# 05_ZYNQ_BANK0_1_34_35.net
KiCad netlist of a schematic drawn in Altium Designer
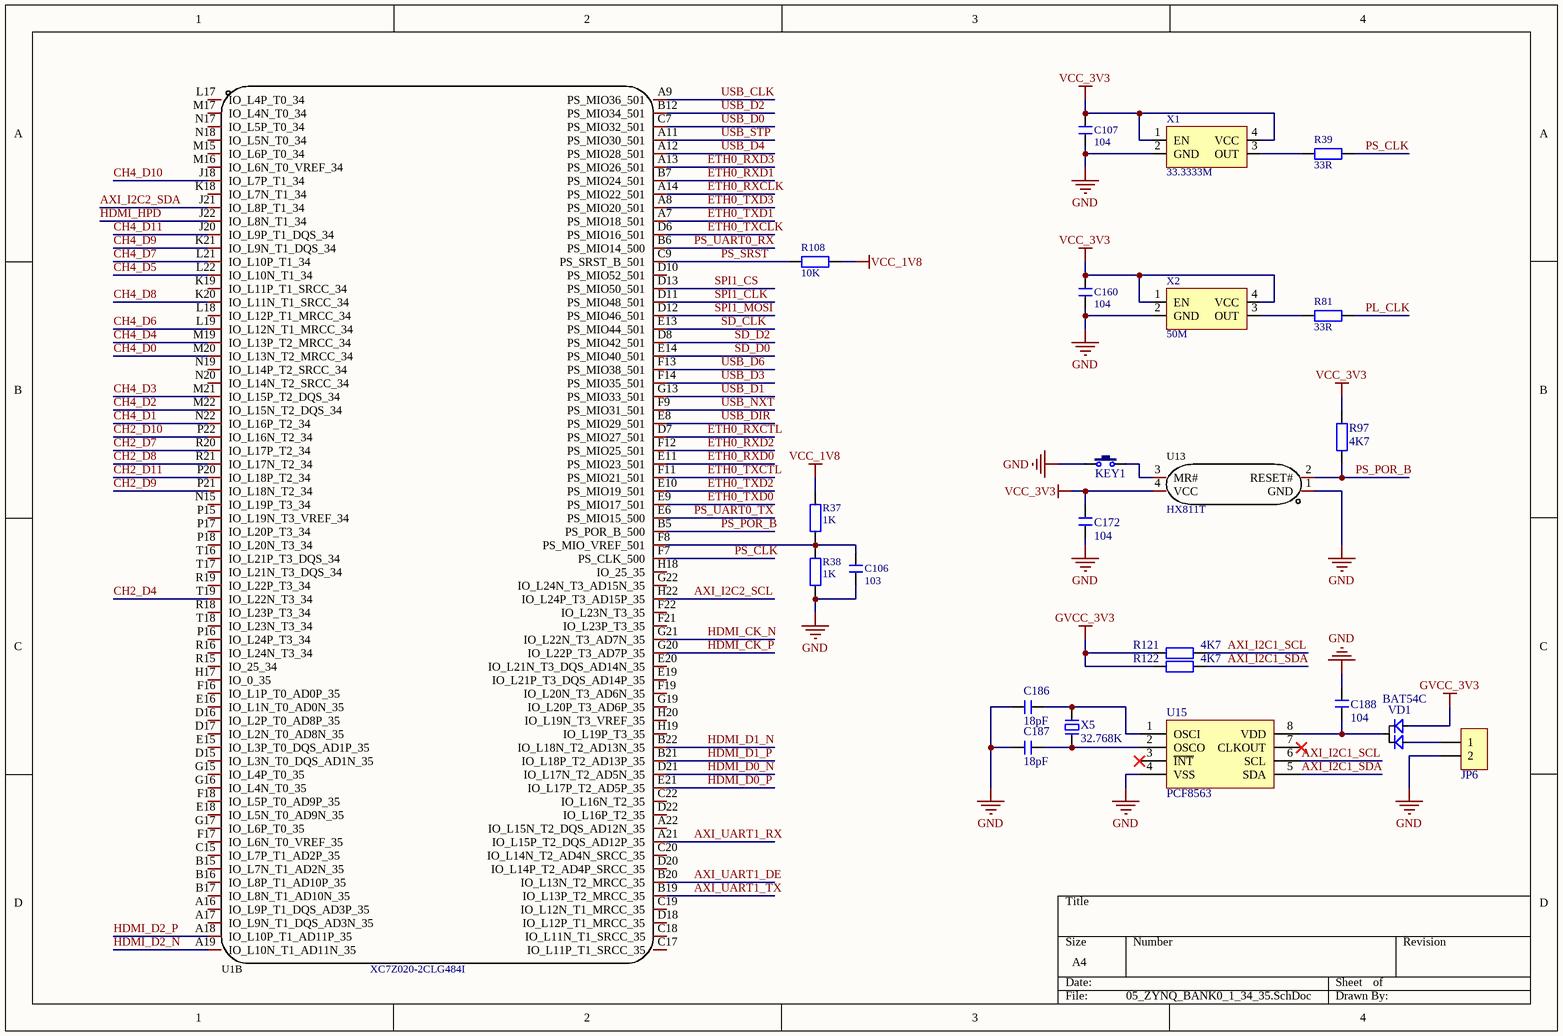
[diagram p0: 05_ZYNQ_BANK0_1_34_35.SchDoc]

(export (version "E")
  (design (tool "Eeschema 10.0.6"))
  (components
    (comp (ref "C106")
      (value "103")
      (footprint "C 0402")
      (description "无极性贴片电容")
      (fields (field (name "版权归属") "源创客"))
      (libsource (lib "STM32MP157核心板封装库V1.2") (part "C"))
    )
    (comp (ref "C107")
      (value "104")
      (footprint "C 0402")
      (description "无极性贴片电容")
      (fields (field (name "版权归属") "源创客"))
      (libsource (lib "STM32MP157核心板封装库V1.2") (part "C"))
    )
    (comp (ref "C160")
      (value "104")
      (footprint "C 0402")
      (description "无极性贴片电容")
      (fields (field (name "版权归属") "源创客"))
      (libsource (lib "STM32MP157核心板封装库V1.2") (part "C"))
    )
    (comp (ref "C172")
      (value "104")
      (footprint "C 0402")
      (description "无极性贴片电容")
      (fields (field (name "版权归属") "源创客"))
      (libsource (lib "STM32MP15x底板封装库V1.4") (part "C"))
    )
    (comp (ref "C186")
      (value "18pF")
      (footprint "C 0603")
      (description "无极性贴片电容")
      (fields (field (name "版权归属") "源创客"))
      (libsource (lib "STM32MP15x底板封装库V1.4") (part "C"))
    )
    (comp (ref "C187")
      (value "18pF")
      (footprint "C 0603")
      (description "无极性贴片电容")
      (fields (field (name "版权归属") "源创客"))
      (libsource (lib "STM32MP15x底板封装库V1.4") (part "C"))
    )
    (comp (ref "C188")
      (value "104")
      (footprint "C 0603")
      (description "无极性贴片电容")
      (fields (field (name "版权归属") "源创客"))
      (libsource (lib "STM32MP15x底板封装库V1.4") (part "C"))
    )
    (comp (ref "JP6")
      (value "HDR-1X2")
      (footprint "SH1.0")
      (description "2P接插件")
      (fields (field (name "版权归属") "源创客"))
      (libsource (lib "4.5   - 接插件-脚距2.54") (part "Header 2"))
    )
    (comp (ref "KEY1")
      (value "KEY")
      (footprint "ButtonTACT_3x4x2_180")
      (description "按键")
      (fields (field (name "版权归属") "源创客"))
      (libsource (lib "STM32MP15x底板封装库V1.4") (part "KEY"))
    )
    (comp (ref "R37")
      (value "1K")
      (footprint "R 0402")
      (description "贴片电阻")
      (fields (field (name "版权归属") "源创客"))
      (libsource (lib "STM32MP157核心板封装库V1.2") (part "R"))
    )
    (comp (ref "R38")
      (value "1K")
      (footprint "R 0402")
      (description "贴片电阻")
      (fields (field (name "版权归属") "源创客"))
      (libsource (lib "STM32MP157核心板封装库V1.2") (part "R"))
    )
    (comp (ref "R39")
      (value "33R")
      (footprint "R 0402")
      (description "贴片电阻")
      (fields (field (name "版权归属") "源创客"))
      (libsource (lib "STM32MP157核心板封装库V1.2") (part "R"))
    )
    (comp (ref "R81")
      (value "33R")
      (footprint "R 0402")
      (description "贴片电阻")
      (fields (field (name "版权归属") "源创客"))
      (libsource (lib "STM32MP157核心板封装库V1.2") (part "R"))
    )
    (comp (ref "R97")
      (value "4K7")
      (footprint "R 0402")
      (description "贴片电阻")
      (fields (field (name "版权归属") "源创客"))
      (libsource (lib "STM32MP15x底板封装库V1.4") (part "R"))
    )
    (comp (ref "R108")
      (value "10K")
      (footprint "R 0402")
      (description "贴片电阻")
      (fields (field (name "版权归属") "源创客"))
      (libsource (lib "STM32MP157核心板封装库V1.2") (part "R"))
    )
    (comp (ref "R121")
      (value "4K7")
      (footprint "R 0603")
      (description "贴片电阻")
      (fields (field (name "版权归属") "源创客"))
      (libsource (lib "STM32MP15x底板封装库V1.4") (part "R"))
    )
    (comp (ref "R122")
      (value "4K7")
      (footprint "R 0603")
      (description "贴片电阻")
      (fields (field (name "版权归属") "源创客"))
      (libsource (lib "STM32MP15x底板封装库V1.4") (part "R"))
    )
    (comp (ref "U1")
      (value "XC7Z020-2CLG484I")
      (footprint "FPBGA-484_L19.0-W19.0-R22-C22-P0.80-BL")
      (fields (field (name "MANUFACTURER") "XILINX(赛灵思)"))
      (libsource (lib "XC7Z020-2CLG484I1") (part "XC7Z020-2CLG484I"))
    )
    (comp (ref "U13")
      (value "HX811T")
      (footprint "SOT143")
      (fields (field (name "MANUFACTURER") "HX(恒佳兴)"))
      (libsource (lib "HX811T") (part "HX811T"))
    )
    (comp (ref "U15")
      (value "PCF8563")
      (footprint "SOP8_N")
      (libsource (lib "STM32MP15x底板封装库V1.4") (part "PCF8563"))
    )
    (comp (ref "VD1")
      (value "BAT54C")
      (footprint "SOT23-3N")
      (description "肖特基二极管（双）")
      (libsource (lib "STM32MP15x底板封装库V1.4") (part "BAT54C"))
    )
    (comp (ref "X1")
      (value "33.3333M")
      (footprint "XTAL-3225 - S")
      (description "4脚有源晶振")
      (fields (field (name "版权归属") "源创客"))
      (libsource (lib "STM32MP157核心板封装库V1.2") (part "XTAL-4P_S"))
    )
    (comp (ref "X2")
      (value "50M")
      (footprint "XTAL-3225 - S")
      (description "4脚有源晶振")
      (fields (field (name "版权归属") "源创客"))
      (libsource (lib "STM32MP157核心板封装库V1.2") (part "XTAL-4P_S"))
    )
    (comp (ref "X5")
      (value "32.768K")
      (footprint "XTAL-3215")
      (description "2脚无源晶振")
      (fields (field (name "版权归属") "源创客"))
      (libsource (lib "STM32MP15x底板封装库V1.4") (part "XTAL-2P"))
    )
  )
  (nets
    (net (code "1") (name "/AXI_I2C1_SCL") (class "Default")
      (node (ref "R121") (pin "2") (pinfunction "2_2") (pintype "passive"))
      (node (ref "U15") (pin "6") (pinfunction "SCL_6") (pintype "passive"))
    )
    (net (code "2") (name "/AXI_I2C1_SDA") (class "Default")
      (node (ref "R122") (pin "2") (pinfunction "2_2") (pintype "passive"))
      (node (ref "U15") (pin "5") (pinfunction "SDA_5") (pintype "passive"))
    )
    (net (code "3") (name "/AXI_I2C2_SCL") (class "Default")
      (node (ref "U1") (pin "H22") (pinfunction "IO_L24P_T3_AD15P_35_H22") (pintype "passive"))
    )
    (net (code "4") (name "/AXI_I2C2_SDA") (class "Default")
      (node (ref "U1") (pin "J21") (pinfunction "IO_L8P_T1_34_J21") (pintype "passive"))
    )
    (net (code "5") (name "/AXI_UART1_DE") (class "Default")
      (node (ref "U1") (pin "B20") (pinfunction "IO_L13N_T2_MRCC_35_B20") (pintype "passive"))
    )
    (net (code "6") (name "/AXI_UART1_RX") (class "Default")
      (node (ref "U1") (pin "A21") (pinfunction "IO_L15P_T2_DQS_AD12P_35_A21") (pintype "passive"))
    )
    (net (code "7") (name "/AXI_UART1_TX") (class "Default")
      (node (ref "U1") (pin "B19") (pinfunction "IO_L13P_T2_MRCC_35_B19") (pintype "passive"))
    )
    (net (code "8") (name "/CH2_D4") (class "Default")
      (node (ref "U1") (pin "T19") (pinfunction "IO_L22N_T3_34_T19") (pintype "passive"))
    )
    (net (code "9") (name "/CH2_D7") (class "Default")
      (node (ref "U1") (pin "R20") (pinfunction "IO_L17P_T2_34_R20") (pintype "passive"))
    )
    (net (code "10") (name "/CH2_D8") (class "Default")
      (node (ref "U1") (pin "R21") (pinfunction "IO_L17N_T2_34_R21") (pintype "passive"))
    )
    (net (code "11") (name "/CH2_D9") (class "Default")
      (node (ref "U1") (pin "P21") (pinfunction "IO_L18N_T2_34_P21") (pintype "passive"))
    )
    (net (code "12") (name "/CH2_D10") (class "Default")
      (node (ref "U1") (pin "P22") (pinfunction "IO_L16N_T2_34_P22") (pintype "passive"))
    )
    (net (code "13") (name "/CH2_D11") (class "Default")
      (node (ref "U1") (pin "P20") (pinfunction "IO_L18P_T2_34_P20") (pintype "passive"))
    )
    (net (code "14") (name "/CH4_D0") (class "Default")
      (node (ref "U1") (pin "M20") (pinfunction "IO_L13N_T2_MRCC_34_M20") (pintype "passive"))
    )
    (net (code "15") (name "/CH4_D1") (class "Default")
      (node (ref "U1") (pin "N22") (pinfunction "IO_L16P_T2_34_N22") (pintype "passive"))
    )
    (net (code "16") (name "/CH4_D2") (class "Default")
      (node (ref "U1") (pin "M22") (pinfunction "IO_L15N_T2_DQS_34_M22") (pintype "passive"))
    )
    (net (code "17") (name "/CH4_D3") (class "Default")
      (node (ref "U1") (pin "M21") (pinfunction "IO_L15P_T2_DQS_34_M21") (pintype "passive"))
    )
    (net (code "18") (name "/CH4_D4") (class "Default")
      (node (ref "U1") (pin "M19") (pinfunction "IO_L13P_T2_MRCC_34_M19") (pintype "passive"))
    )
    (net (code "19") (name "/CH4_D5") (class "Default")
      (node (ref "U1") (pin "L22") (pinfunction "IO_L10N_T1_34_L22") (pintype "passive"))
    )
    (net (code "20") (name "/CH4_D6") (class "Default")
      (node (ref "U1") (pin "L19") (pinfunction "IO_L12N_T1_MRCC_34_L19") (pintype "passive"))
    )
    (net (code "21") (name "/CH4_D7") (class "Default")
      (node (ref "U1") (pin "L21") (pinfunction "IO_L10P_T1_34_L21") (pintype "passive"))
    )
    (net (code "22") (name "/CH4_D8") (class "Default")
      (node (ref "U1") (pin "K20") (pinfunction "IO_L11N_T1_SRCC_34_K20") (pintype "passive"))
    )
    (net (code "23") (name "/CH4_D9") (class "Default")
      (node (ref "U1") (pin "K21") (pinfunction "IO_L9N_T1_DQS_34_K21") (pintype "passive"))
    )
    (net (code "24") (name "/CH4_D10") (class "Default")
      (node (ref "U1") (pin "J18") (pinfunction "IO_L7P_T1_34_J18") (pintype "passive"))
    )
    (net (code "25") (name "/CH4_D11") (class "Default")
      (node (ref "U1") (pin "J20") (pinfunction "IO_L9P_T1_DQS_34_J20") (pintype "passive"))
    )
    (net (code "26") (name "/ETH0_RXCLK") (class "Default")
      (node (ref "U1") (pin "A14") (pinfunction "PS_MIO22_501_A14") (pintype "passive"))
    )
    (net (code "27") (name "/ETH0_RXCTL") (class "Default")
      (node (ref "U1") (pin "D7") (pinfunction "PS_MIO27_501_D7") (pintype "passive"))
    )
    (net (code "28") (name "/ETH0_RXD0") (class "Default")
      (node (ref "U1") (pin "E11") (pinfunction "PS_MIO23_501_E11") (pintype "passive"))
    )
    (net (code "29") (name "/ETH0_RXD1") (class "Default")
      (node (ref "U1") (pin "B7") (pinfunction "PS_MIO24_501_B7") (pintype "passive"))
    )
    (net (code "30") (name "/ETH0_RXD2") (class "Default")
      (node (ref "U1") (pin "F12") (pinfunction "PS_MIO25_501_F12") (pintype "passive"))
    )
    (net (code "31") (name "/ETH0_RXD3") (class "Default")
      (node (ref "U1") (pin "A13") (pinfunction "PS_MIO26_501_A13") (pintype "passive"))
    )
    (net (code "32") (name "/ETH0_TXCLK") (class "Default")
      (node (ref "U1") (pin "D6") (pinfunction "PS_MIO16_501_D6") (pintype "passive"))
    )
    (net (code "33") (name "/ETH0_TXCTL") (class "Default")
      (node (ref "U1") (pin "F11") (pinfunction "PS_MIO21_501_F11") (pintype "passive"))
    )
    (net (code "34") (name "/ETH0_TXD0") (class "Default")
      (node (ref "U1") (pin "E9") (pinfunction "PS_MIO17_501_E9") (pintype "passive"))
    )
    (net (code "35") (name "/ETH0_TXD1") (class "Default")
      (node (ref "U1") (pin "A7") (pinfunction "PS_MIO18_501_A7") (pintype "passive"))
    )
    (net (code "36") (name "/ETH0_TXD2") (class "Default")
      (node (ref "U1") (pin "E10") (pinfunction "PS_MIO19_501_E10") (pintype "passive"))
    )
    (net (code "37") (name "/ETH0_TXD3") (class "Default")
      (node (ref "U1") (pin "A8") (pinfunction "PS_MIO20_501_A8") (pintype "passive"))
    )
    (net (code "38") (name "/HDMI_CK_N") (class "Default")
      (node (ref "U1") (pin "G21") (pinfunction "IO_L22N_T3_AD7N_35_G21") (pintype "passive"))
    )
    (net (code "39") (name "/HDMI_CK_P") (class "Default")
      (node (ref "U1") (pin "G20") (pinfunction "IO_L22P_T3_AD7P_35_G20") (pintype "passive"))
    )
    (net (code "40") (name "/HDMI_D0_N") (class "Default")
      (node (ref "U1") (pin "D21") (pinfunction "IO_L17N_T2_AD5N_35_D21") (pintype "passive"))
    )
    (net (code "41") (name "/HDMI_D0_P") (class "Default")
      (node (ref "U1") (pin "E21") (pinfunction "IO_L17P_T2_AD5P_35_E21") (pintype "passive"))
    )
    (net (code "42") (name "/HDMI_D1_N") (class "Default")
      (node (ref "U1") (pin "B22") (pinfunction "IO_L18N_T2_AD13N_35_B22") (pintype "passive"))
    )
    (net (code "43") (name "/HDMI_D1_P") (class "Default")
      (node (ref "U1") (pin "B21") (pinfunction "IO_L18P_T2_AD13P_35_B21") (pintype "passive"))
    )
    (net (code "44") (name "/HDMI_D2_N") (class "Default")
      (node (ref "U1") (pin "A19") (pinfunction "IO_L10N_T1_AD11N_35_A19") (pintype "passive"))
    )
    (net (code "45") (name "/HDMI_D2_P") (class "Default")
      (node (ref "U1") (pin "A18") (pinfunction "IO_L10P_T1_AD11P_35_A18") (pintype "passive"))
    )
    (net (code "46") (name "/HDMI_HPD") (class "Default")
      (node (ref "U1") (pin "J22") (pinfunction "IO_L8N_T1_34_J22") (pintype "passive"))
    )
    (net (code "47") (name "/PL_CLK") (class "Default")
      (node (ref "R81") (pin "2") (pinfunction "2_2") (pintype "passive"))
    )
    (net (code "48") (name "/PS_CLK") (class "Default")
      (node (ref "R39") (pin "2") (pinfunction "2_2") (pintype "passive"))
      (node (ref "U1") (pin "F7") (pinfunction "PS_CLK_500_F7") (pintype "passive"))
    )
    (net (code "49") (name "/PS_POR_B") (class "Default")
      (node (ref "R97") (pin "1") (pinfunction "1_1") (pintype "passive"))
      (node (ref "U1") (pin "B5") (pinfunction "PS_POR_B_500_B5") (pintype "passive"))
      (node (ref "U13") (pin "2") (pinfunction "RESET#_2") (pintype "passive"))
    )
    (net (code "50") (name "/PS_SRST") (class "Default")
      (node (ref "R108") (pin "2") (pinfunction "2_2") (pintype "passive"))
      (node (ref "U1") (pin "C9") (pinfunction "PS_SRST_B_501_C9") (pintype "passive"))
    )
    (net (code "51") (name "/PS_UART0_RX") (class "Default")
      (node (ref "U1") (pin "B6") (pinfunction "PS_MIO14_500_B6") (pintype "passive"))
    )
    (net (code "52") (name "/PS_UART0_TX") (class "Default")
      (node (ref "U1") (pin "E6") (pinfunction "PS_MIO15_500_E6") (pintype "passive"))
    )
    (net (code "53") (name "/SD_CLK") (class "Default")
      (node (ref "U1") (pin "E13") (pinfunction "PS_MIO44_501_E13") (pintype "passive"))
    )
    (net (code "54") (name "/SD_D0") (class "Default")
      (node (ref "U1") (pin "E14") (pinfunction "PS_MIO40_501_E14") (pintype "passive"))
    )
    (net (code "55") (name "/SD_D2") (class "Default")
      (node (ref "U1") (pin "D8") (pinfunction "PS_MIO42_501_D8") (pintype "passive"))
    )
    (net (code "56") (name "/SPI1_CLK") (class "Default")
      (node (ref "U1") (pin "D11") (pinfunction "PS_MIO48_501_D11") (pintype "passive"))
    )
    (net (code "57") (name "/SPI1_CS") (class "Default")
      (node (ref "U1") (pin "D13") (pinfunction "PS_MIO50_501_D13") (pintype "passive"))
    )
    (net (code "58") (name "/SPI1_MOSI") (class "Default")
      (node (ref "U1") (pin "D12") (pinfunction "PS_MIO46_501_D12") (pintype "passive"))
    )
    (net (code "59") (name "/USB_CLK") (class "Default")
      (node (ref "U1") (pin "A9") (pinfunction "PS_MIO36_501_A9") (pintype "passive"))
    )
    (net (code "60") (name "/USB_D0") (class "Default")
      (node (ref "U1") (pin "C7") (pinfunction "PS_MIO32_501_C7") (pintype "passive"))
    )
    (net (code "61") (name "/USB_D1") (class "Default")
      (node (ref "U1") (pin "G13") (pinfunction "PS_MIO33_501_G13") (pintype "passive"))
    )
    (net (code "62") (name "/USB_D2") (class "Default")
      (node (ref "U1") (pin "B12") (pinfunction "PS_MIO34_501_B12") (pintype "passive"))
    )
    (net (code "63") (name "/USB_D3") (class "Default")
      (node (ref "U1") (pin "F14") (pinfunction "PS_MIO35_501_F14") (pintype "passive"))
    )
    (net (code "64") (name "/USB_D4") (class "Default")
      (node (ref "U1") (pin "A12") (pinfunction "PS_MIO28_501_A12") (pintype "passive"))
    )
    (net (code "65") (name "/USB_D6") (class "Default")
      (node (ref "U1") (pin "F13") (pinfunction "PS_MIO38_501_F13") (pintype "passive"))
    )
    (net (code "66") (name "/USB_DIR") (class "Default")
      (node (ref "U1") (pin "E8") (pinfunction "PS_MIO29_501_E8") (pintype "passive"))
    )
    (net (code "67") (name "/USB_NXT") (class "Default")
      (node (ref "U1") (pin "F9") (pinfunction "PS_MIO31_501_F9") (pintype "passive"))
    )
    (net (code "68") (name "/USB_STP") (class "Default")
      (node (ref "U1") (pin "A11") (pinfunction "PS_MIO30_501_A11") (pintype "passive"))
    )
    (net (code "69") (name "GND") (class "Default")
      (node (ref "C106") (pin "1") (pinfunction "1_1") (pintype "passive"))
      (node (ref "C107") (pin "1") (pinfunction "1_1") (pintype "passive"))
      (node (ref "C160") (pin "1") (pinfunction "1_1") (pintype "passive"))
      (node (ref "C172") (pin "1") (pinfunction "1_1") (pintype "passive"))
      (node (ref "C186") (pin "2") (pinfunction "2_2") (pintype "passive"))
      (node (ref "C187") (pin "2") (pinfunction "2_2") (pintype "passive"))
      (node (ref "C188") (pin "2") (pinfunction "2_2") (pintype "passive"))
      (node (ref "JP6") (pin "2") (pinfunction "2_2") (pintype "passive"))
      (node (ref "KEY1") (pin "1") (pinfunction "1_1") (pintype "passive"))
      (node (ref "R38") (pin "1") (pinfunction "1_1") (pintype "passive"))
      (node (ref "U13") (pin "1") (pinfunction "GND_1") (pintype "passive"))
      (node (ref "U15") (pin "4") (pinfunction "VSS_4") (pintype "passive"))
      (node (ref "X1") (pin "2") (pinfunction "GND_2") (pintype "passive"))
      (node (ref "X2") (pin "2") (pinfunction "GND_2") (pintype "passive"))
    )
    (net (code "70") (name "GVCC_3V3") (class "Default")
      (node (ref "R121") (pin "1") (pinfunction "1_1") (pintype "passive"))
      (node (ref "R122") (pin "1") (pinfunction "1_1") (pintype "passive"))
      (node (ref "VD1") (pin "2") (pinfunction "2_2") (pintype "passive"))
    )
    (net (code "71") (name "Net-(JP6-Pad1)") (class "Default")
      (node (ref "JP6") (pin "1") (pinfunction "1_1") (pintype "passive"))
      (node (ref "VD1") (pin "1") (pinfunction "1_1") (pintype "passive"))
    )
    (net (code "72") (name "Net-(U1B-PS_MIO_VREF_501)") (class "Default")
      (node (ref "C106") (pin "2") (pinfunction "2_2") (pintype "passive"))
      (node (ref "R37") (pin "1") (pinfunction "1_1") (pintype "passive"))
      (node (ref "R38") (pin "2") (pinfunction "2_2") (pintype "passive"))
      (node (ref "U1") (pin "F8") (pinfunction "PS_MIO_VREF_501_F8") (pintype "passive"))
    )
    (net (code "73") (name "Net-(U13-MR#)") (class "Default")
      (node (ref "KEY1") (pin "2") (pinfunction "2_2") (pintype "passive"))
      (node (ref "U13") (pin "3") (pinfunction "MR#_3") (pintype "passive"))
    )
    (net (code "74") (name "Net-(U15-OSCI)") (class "Default")
      (node (ref "C186") (pin "1") (pinfunction "1_1") (pintype "passive"))
      (node (ref "U15") (pin "1") (pinfunction "OSCI_1") (pintype "passive"))
      (node (ref "X5") (pin "1") (pinfunction "1_1") (pintype "passive"))
    )
    (net (code "75") (name "Net-(U15-OSCO)") (class "Default")
      (node (ref "C187") (pin "1") (pinfunction "1_1") (pintype "passive"))
      (node (ref "U15") (pin "2") (pinfunction "OSCO_2") (pintype "passive"))
      (node (ref "X5") (pin "2") (pinfunction "2_2") (pintype "passive"))
    )
    (net (code "76") (name "Net-(U15-VDD)") (class "Default")
      (node (ref "C188") (pin "1") (pinfunction "1_1") (pintype "passive"))
      (node (ref "U15") (pin "8") (pinfunction "VDD_8") (pintype "passive"))
      (node (ref "VD1") (pin "3") (pinfunction "3_3") (pintype "passive"))
    )
    (net (code "77") (name "Net-(X1-OUT)") (class "Default")
      (node (ref "R39") (pin "1") (pinfunction "1_1") (pintype "passive"))
      (node (ref "X1") (pin "3") (pinfunction "OUT_3") (pintype "passive"))
    )
    (net (code "78") (name "Net-(X2-OUT)") (class "Default")
      (node (ref "R81") (pin "1") (pinfunction "1_1") (pintype "passive"))
      (node (ref "X2") (pin "3") (pinfunction "OUT_3") (pintype "passive"))
    )
    (net (code "79") (name "VCC_1V8") (class "Default")
      (node (ref "R108") (pin "1") (pinfunction "1_1") (pintype "passive"))
      (node (ref "R37") (pin "2") (pinfunction "2_2") (pintype "passive"))
    )
    (net (code "80") (name "VCC_3V3") (class "Default")
      (node (ref "C107") (pin "2") (pinfunction "2_2") (pintype "passive"))
      (node (ref "C160") (pin "2") (pinfunction "2_2") (pintype "passive"))
      (node (ref "C172") (pin "2") (pinfunction "2_2") (pintype "passive"))
      (node (ref "R97") (pin "2") (pinfunction "2_2") (pintype "passive"))
      (node (ref "U13") (pin "4") (pinfunction "VCC_4") (pintype "passive"))
      (node (ref "X1") (pin "1") (pinfunction "EN_1") (pintype "passive"))
      (node (ref "X1") (pin "4") (pinfunction "VCC_4") (pintype "passive"))
      (node (ref "X2") (pin "1") (pinfunction "EN_1") (pintype "passive"))
      (node (ref "X2") (pin "4") (pinfunction "VCC_4") (pintype "passive"))
    )
    (net (code "81") (name "unconnected-(U1B-IO_0_35-PadH17)") (class "Default")
      (node (ref "U1") (pin "H17") (pinfunction "IO_0_35_H17") (pintype "passive"))
    )
    (net (code "82") (name "unconnected-(U1B-IO_25_34-PadR15)") (class "Default")
      (node (ref "U1") (pin "R15") (pinfunction "IO_25_34_R15") (pintype "passive"))
    )
    (net (code "83") (name "unconnected-(U1B-IO_25_35-PadH18)") (class "Default")
      (node (ref "U1") (pin "H18") (pinfunction "IO_25_35_H18") (pintype "passive"))
    )
    (net (code "84") (name "unconnected-(U1B-IO_L1N_T0_AD0N_35-PadE16)") (class "Default")
      (node (ref "U1") (pin "E16") (pinfunction "IO_L1N_T0_AD0N_35_E16") (pintype "passive"))
    )
    (net (code "85") (name "unconnected-(U1B-IO_L1P_T0_AD0P_35-PadF16)") (class "Default")
      (node (ref "U1") (pin "F16") (pinfunction "IO_L1P_T0_AD0P_35_F16") (pintype "passive"))
    )
    (net (code "86") (name "unconnected-(U1B-IO_L2N_T0_AD8N_35-PadD17)") (class "Default")
      (node (ref "U1") (pin "D17") (pinfunction "IO_L2N_T0_AD8N_35_D17") (pintype "passive"))
    )
    (net (code "87") (name "unconnected-(U1B-IO_L2P_T0_AD8P_35-PadD16)") (class "Default")
      (node (ref "U1") (pin "D16") (pinfunction "IO_L2P_T0_AD8P_35_D16") (pintype "passive"))
    )
    (net (code "88") (name "unconnected-(U1B-IO_L3N_T0_DQS_AD1N_35-PadD15)") (class "Default")
      (node (ref "U1") (pin "D15") (pinfunction "IO_L3N_T0_DQS_AD1N_35_D15") (pintype "passive"))
    )
    (net (code "89") (name "unconnected-(U1B-IO_L3P_T0_DQS_AD1P_35-PadE15)") (class "Default")
      (node (ref "U1") (pin "E15") (pinfunction "IO_L3P_T0_DQS_AD1P_35_E15") (pintype "passive"))
    )
    (net (code "90") (name "unconnected-(U1B-IO_L4N_T0_34-PadM17)") (class "Default")
      (node (ref "U1") (pin "M17") (pinfunction "IO_L4N_T0_34_M17") (pintype "passive"))
    )
    (net (code "91") (name "unconnected-(U1B-IO_L4N_T0_35-PadG16)") (class "Default")
      (node (ref "U1") (pin "G16") (pinfunction "IO_L4N_T0_35_G16") (pintype "passive"))
    )
    (net (code "92") (name "unconnected-(U1B-IO_L4P_T0_34-PadL17)") (class "Default")
      (node (ref "U1") (pin "L17") (pinfunction "IO_L4P_T0_34_L17") (pintype "passive"))
    )
    (net (code "93") (name "unconnected-(U1B-IO_L4P_T0_35-PadG15)") (class "Default")
      (node (ref "U1") (pin "G15") (pinfunction "IO_L4P_T0_35_G15") (pintype "passive"))
    )
    (net (code "94") (name "unconnected-(U1B-IO_L5N_T0_34-PadN18)") (class "Default")
      (node (ref "U1") (pin "N18") (pinfunction "IO_L5N_T0_34_N18") (pintype "passive"))
    )
    (net (code "95") (name "unconnected-(U1B-IO_L5N_T0_AD9N_35-PadE18)") (class "Default")
      (node (ref "U1") (pin "E18") (pinfunction "IO_L5N_T0_AD9N_35_E18") (pintype "passive"))
    )
    (net (code "96") (name "unconnected-(U1B-IO_L5P_T0_34-PadN17)") (class "Default")
      (node (ref "U1") (pin "N17") (pinfunction "IO_L5P_T0_34_N17") (pintype "passive"))
    )
    (net (code "97") (name "unconnected-(U1B-IO_L5P_T0_AD9P_35-PadF18)") (class "Default")
      (node (ref "U1") (pin "F18") (pinfunction "IO_L5P_T0_AD9P_35_F18") (pintype "passive"))
    )
    (net (code "98") (name "unconnected-(U1B-IO_L6N_T0_VREF_34-PadM16)") (class "Default")
      (node (ref "U1") (pin "M16") (pinfunction "IO_L6N_T0_VREF_34_M16") (pintype "passive"))
    )
    (net (code "99") (name "unconnected-(U1B-IO_L6N_T0_VREF_35-PadF17)") (class "Default")
      (node (ref "U1") (pin "F17") (pinfunction "IO_L6N_T0_VREF_35_F17") (pintype "passive"))
    )
    (net (code "100") (name "unconnected-(U1B-IO_L6P_T0_34-PadM15)") (class "Default")
      (node (ref "U1") (pin "M15") (pinfunction "IO_L6P_T0_34_M15") (pintype "passive"))
    )
    (net (code "101") (name "unconnected-(U1B-IO_L6P_T0_35-PadG17)") (class "Default")
      (node (ref "U1") (pin "G17") (pinfunction "IO_L6P_T0_35_G17") (pintype "passive"))
    )
    (net (code "102") (name "unconnected-(U1B-IO_L7N_T1_34-PadK18)") (class "Default")
      (node (ref "U1") (pin "K18") (pinfunction "IO_L7N_T1_34_K18") (pintype "passive"))
    )
    (net (code "103") (name "unconnected-(U1B-IO_L7N_T1_AD2N_35-PadB15)") (class "Default")
      (node (ref "U1") (pin "B15") (pinfunction "IO_L7N_T1_AD2N_35_B15") (pintype "passive"))
    )
    (net (code "104") (name "unconnected-(U1B-IO_L7P_T1_AD2P_35-PadC15)") (class "Default")
      (node (ref "U1") (pin "C15") (pinfunction "IO_L7P_T1_AD2P_35_C15") (pintype "passive"))
    )
    (net (code "105") (name "unconnected-(U1B-IO_L8N_T1_AD10N_35-PadB17)") (class "Default")
      (node (ref "U1") (pin "B17") (pinfunction "IO_L8N_T1_AD10N_35_B17") (pintype "passive"))
    )
    (net (code "106") (name "unconnected-(U1B-IO_L8P_T1_AD10P_35-PadB16)") (class "Default")
      (node (ref "U1") (pin "B16") (pinfunction "IO_L8P_T1_AD10P_35_B16") (pintype "passive"))
    )
    (net (code "107") (name "unconnected-(U1B-IO_L9N_T1_DQS_AD3N_35-PadA17)") (class "Default")
      (node (ref "U1") (pin "A17") (pinfunction "IO_L9N_T1_DQS_AD3N_35_A17") (pintype "passive"))
    )
    (net (code "108") (name "unconnected-(U1B-IO_L9P_T1_DQS_AD3P_35-PadA16)") (class "Default")
      (node (ref "U1") (pin "A16") (pinfunction "IO_L9P_T1_DQS_AD3P_35_A16") (pintype "passive"))
    )
    (net (code "109") (name "unconnected-(U1B-IO_L11N_T1_SRCC_35-PadC18)") (class "Default")
      (node (ref "U1") (pin "C18") (pinfunction "IO_L11N_T1_SRCC_35_C18") (pintype "passive"))
    )
    (net (code "110") (name "unconnected-(U1B-IO_L11P_T1_SRCC_34-PadK19)") (class "Default")
      (node (ref "U1") (pin "K19") (pinfunction "IO_L11P_T1_SRCC_34_K19") (pintype "passive"))
    )
    (net (code "111") (name "unconnected-(U1B-IO_L11P_T1_SRCC_35-PadC17)") (class "Default")
      (node (ref "U1") (pin "C17") (pinfunction "IO_L11P_T1_SRCC_35_C17") (pintype "passive"))
    )
    (net (code "112") (name "unconnected-(U1B-IO_L12N_T1_MRCC_35-PadC19)") (class "Default")
      (node (ref "U1") (pin "C19") (pinfunction "IO_L12N_T1_MRCC_35_C19") (pintype "passive"))
    )
    (net (code "113") (name "unconnected-(U1B-IO_L12P_T1_MRCC_34-PadL18)") (class "Default")
      (node (ref "U1") (pin "L18") (pinfunction "IO_L12P_T1_MRCC_34_L18") (pintype "passive"))
    )
    (net (code "114") (name "unconnected-(U1B-IO_L12P_T1_MRCC_35-PadD18)") (class "Default")
      (node (ref "U1") (pin "D18") (pinfunction "IO_L12P_T1_MRCC_35_D18") (pintype "passive"))
    )
    (net (code "115") (name "unconnected-(U1B-IO_L14N_T2_AD4N_SRCC_35-PadC20)") (class "Default")
      (node (ref "U1") (pin "C20") (pinfunction "IO_L14N_T2_AD4N_SRCC_35_C20") (pintype "passive"))
    )
    (net (code "116") (name "unconnected-(U1B-IO_L14N_T2_SRCC_34-PadN20)") (class "Default")
      (node (ref "U1") (pin "N20") (pinfunction "IO_L14N_T2_SRCC_34_N20") (pintype "passive"))
    )
    (net (code "117") (name "unconnected-(U1B-IO_L14P_T2_AD4P_SRCC_35-PadD20)") (class "Default")
      (node (ref "U1") (pin "D20") (pinfunction "IO_L14P_T2_AD4P_SRCC_35_D20") (pintype "passive"))
    )
    (net (code "118") (name "unconnected-(U1B-IO_L14P_T2_SRCC_34-PadN19)") (class "Default")
      (node (ref "U1") (pin "N19") (pinfunction "IO_L14P_T2_SRCC_34_N19") (pintype "passive"))
    )
    (net (code "119") (name "unconnected-(U1B-IO_L15N_T2_DQS_AD12N_35-PadA22)") (class "Default")
      (node (ref "U1") (pin "A22") (pinfunction "IO_L15N_T2_DQS_AD12N_35_A22") (pintype "passive"))
    )
    (net (code "120") (name "unconnected-(U1B-IO_L16N_T2_35-PadC22)") (class "Default")
      (node (ref "U1") (pin "C22") (pinfunction "IO_L16N_T2_35_C22") (pintype "passive"))
    )
    (net (code "121") (name "unconnected-(U1B-IO_L16P_T2_35-PadD22)") (class "Default")
      (node (ref "U1") (pin "D22") (pinfunction "IO_L16P_T2_35_D22") (pintype "passive"))
    )
    (net (code "122") (name "unconnected-(U1B-IO_L19N_T3_VREF_34-PadP15)") (class "Default")
      (node (ref "U1") (pin "P15") (pinfunction "IO_L19N_T3_VREF_34_P15") (pintype "passive"))
    )
    (net (code "123") (name "unconnected-(U1B-IO_L19N_T3_VREF_35-PadH20)") (class "Default")
      (node (ref "U1") (pin "H20") (pinfunction "IO_L19N_T3_VREF_35_H20") (pintype "passive"))
    )
    (net (code "124") (name "unconnected-(U1B-IO_L19P_T3_34-PadN15)") (class "Default")
      (node (ref "U1") (pin "N15") (pinfunction "IO_L19P_T3_34_N15") (pintype "passive"))
    )
    (net (code "125") (name "unconnected-(U1B-IO_L19P_T3_35-PadH19)") (class "Default")
      (node (ref "U1") (pin "H19") (pinfunction "IO_L19P_T3_35_H19") (pintype "passive"))
    )
    (net (code "126") (name "unconnected-(U1B-IO_L20N_T3_34-PadP18)") (class "Default")
      (node (ref "U1") (pin "P18") (pinfunction "IO_L20N_T3_34_P18") (pintype "passive"))
    )
    (net (code "127") (name "unconnected-(U1B-IO_L20N_T3_AD6N_35-PadF19)") (class "Default")
      (node (ref "U1") (pin "F19") (pinfunction "IO_L20N_T3_AD6N_35_F19") (pintype "passive"))
    )
    (net (code "128") (name "unconnected-(U1B-IO_L20P_T3_34-PadP17)") (class "Default")
      (node (ref "U1") (pin "P17") (pinfunction "IO_L20P_T3_34_P17") (pintype "passive"))
    )
    (net (code "129") (name "unconnected-(U1B-IO_L20P_T3_AD6P_35-PadG19)") (class "Default")
      (node (ref "U1") (pin "G19") (pinfunction "IO_L20P_T3_AD6P_35_G19") (pintype "passive"))
    )
    (net (code "130") (name "unconnected-(U1B-IO_L21N_T3_DQS_34-PadT17)") (class "Default")
      (node (ref "U1") (pin "T17") (pinfunction "IO_L21N_T3_DQS_34_T17") (pintype "passive"))
    )
    (net (code "131") (name "unconnected-(U1B-IO_L21N_T3_DQS_AD14N_35-PadE20)") (class "Default")
      (node (ref "U1") (pin "E20") (pinfunction "IO_L21N_T3_DQS_AD14N_35_E20") (pintype "passive"))
    )
    (net (code "132") (name "unconnected-(U1B-IO_L21P_T3_DQS_34-PadT16)") (class "Default")
      (node (ref "U1") (pin "T16") (pinfunction "IO_L21P_T3_DQS_34_T16") (pintype "passive"))
    )
    (net (code "133") (name "unconnected-(U1B-IO_L21P_T3_DQS_AD14P_35-PadE19)") (class "Default")
      (node (ref "U1") (pin "E19") (pinfunction "IO_L21P_T3_DQS_AD14P_35_E19") (pintype "passive"))
    )
    (net (code "134") (name "unconnected-(U1B-IO_L22P_T3_34-PadR19)") (class "Default")
      (node (ref "U1") (pin "R19") (pinfunction "IO_L22P_T3_34_R19") (pintype "passive"))
    )
    (net (code "135") (name "unconnected-(U1B-IO_L23N_T3_34-PadT18)") (class "Default")
      (node (ref "U1") (pin "T18") (pinfunction "IO_L23N_T3_34_T18") (pintype "passive"))
    )
    (net (code "136") (name "unconnected-(U1B-IO_L23N_T3_35-PadF22)") (class "Default")
      (node (ref "U1") (pin "F22") (pinfunction "IO_L23N_T3_35_F22") (pintype "passive"))
    )
    (net (code "137") (name "unconnected-(U1B-IO_L23P_T3_34-PadR18)") (class "Default")
      (node (ref "U1") (pin "R18") (pinfunction "IO_L23P_T3_34_R18") (pintype "passive"))
    )
    (net (code "138") (name "unconnected-(U1B-IO_L23P_T3_35-PadF21)") (class "Default")
      (node (ref "U1") (pin "F21") (pinfunction "IO_L23P_T3_35_F21") (pintype "passive"))
    )
    (net (code "139") (name "unconnected-(U1B-IO_L24N_T3_34-PadR16)") (class "Default")
      (node (ref "U1") (pin "R16") (pinfunction "IO_L24N_T3_34_R16") (pintype "passive"))
    )
    (net (code "140") (name "unconnected-(U1B-IO_L24N_T3_AD15N_35-PadG22)") (class "Default")
      (node (ref "U1") (pin "G22") (pinfunction "IO_L24N_T3_AD15N_35_G22") (pintype "passive"))
    )
    (net (code "141") (name "unconnected-(U1B-IO_L24P_T3_34-PadP16)") (class "Default")
      (node (ref "U1") (pin "P16") (pinfunction "IO_L24P_T3_34_P16") (pintype "passive"))
    )
    (net (code "142") (name "unconnected-(U1B-PS_MIO52_501-PadD10)") (class "Default")
      (node (ref "U1") (pin "D10") (pinfunction "PS_MIO52_501_D10") (pintype "passive"))
    )
    (net (code "143") (name "unconnected-(U15-CLKOUT-Pad7)") (class "Default")
      (node (ref "U15") (pin "7") (pinfunction "CLKOUT_7") (pintype "passive+no_connect"))
    )
    (net (code "144") (name "unconnected-(U15-~{INT}-Pad3)") (class "Default")
      (node (ref "U15") (pin "3") (pinfunction "~{INT}_3") (pintype "passive+no_connect"))
    )
  )
)
